# uWave.net
KiCad netlist of a schematic drawn in EAGLE
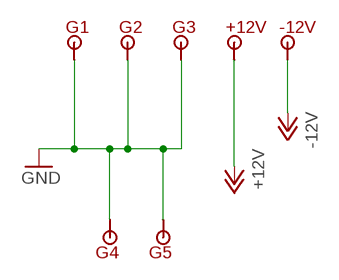
[diagram p0: schematic, sheet 1]
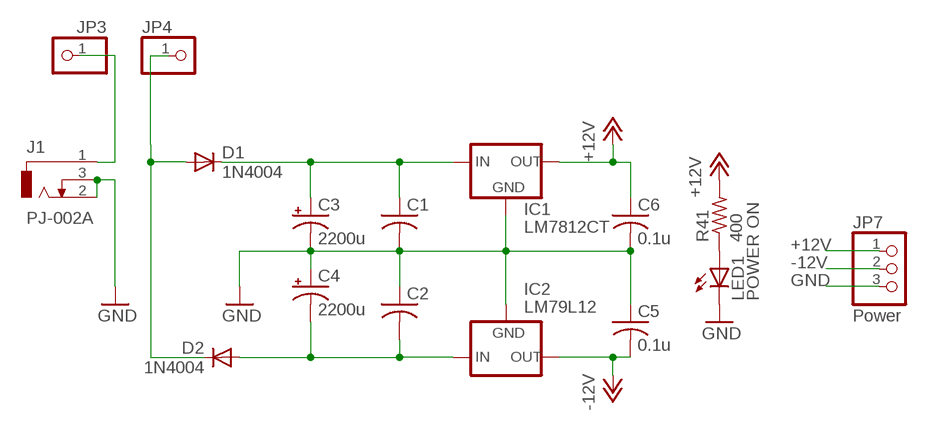
[diagram p1: schematic, sheet 2]
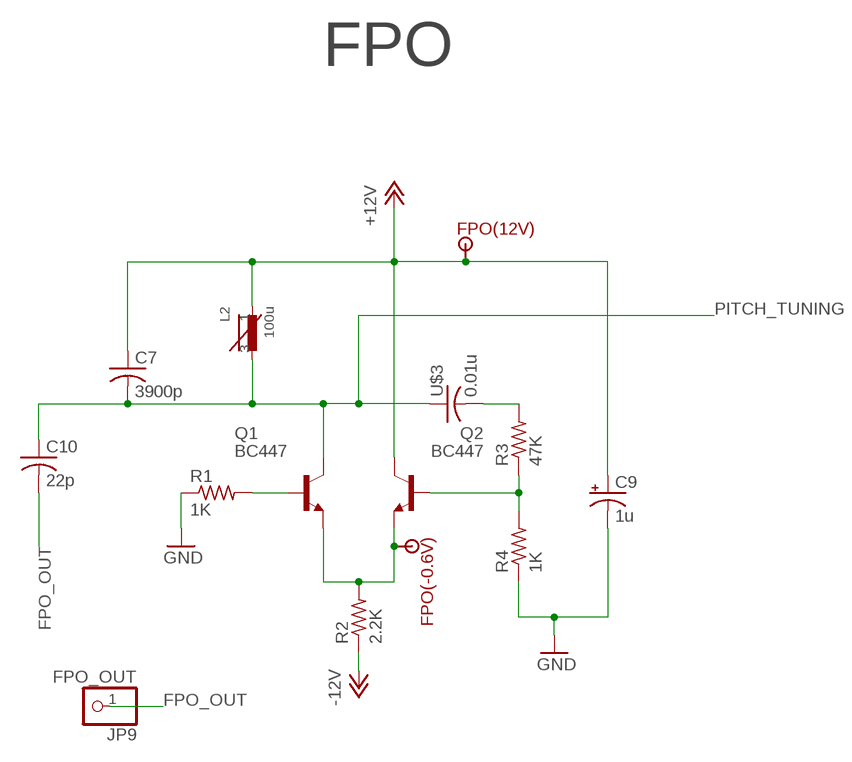
[diagram p2: schematic, sheet 3]
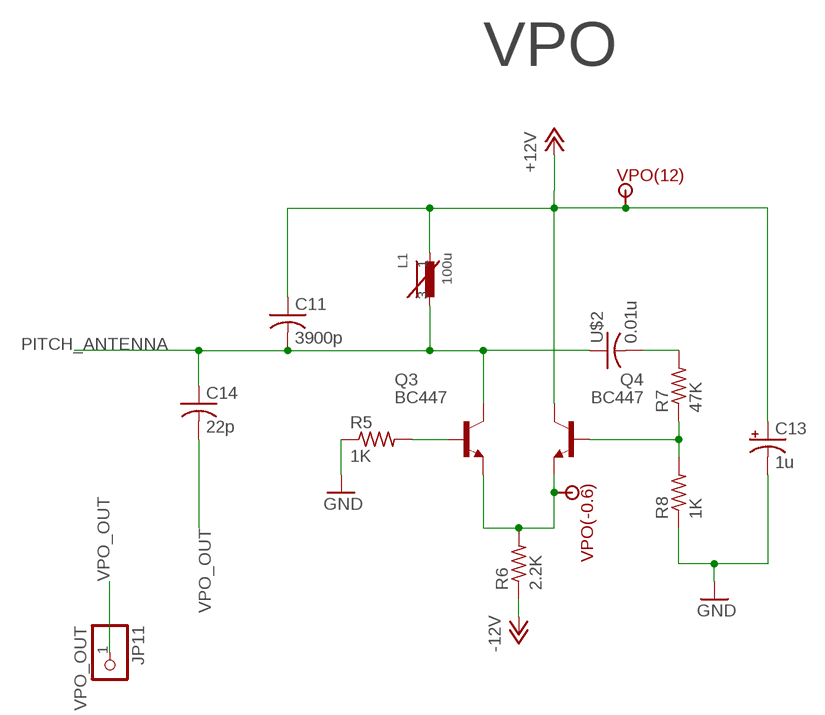
[diagram p3: schematic, sheet 4]
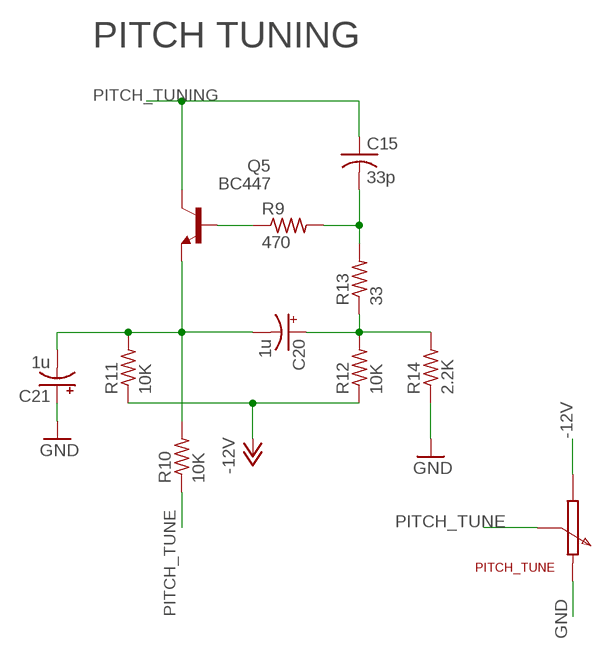
[diagram p4: schematic, sheet 5]
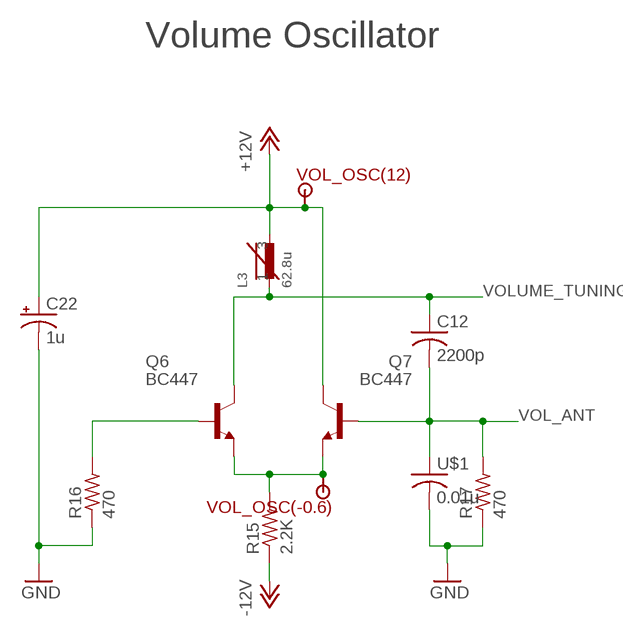
[diagram p5: schematic, sheet 6]
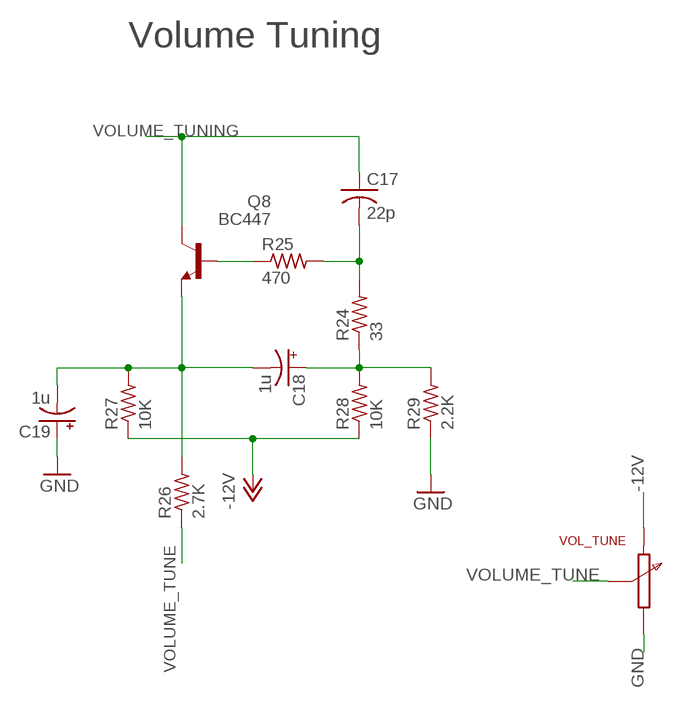
[diagram p6: schematic, sheet 7]
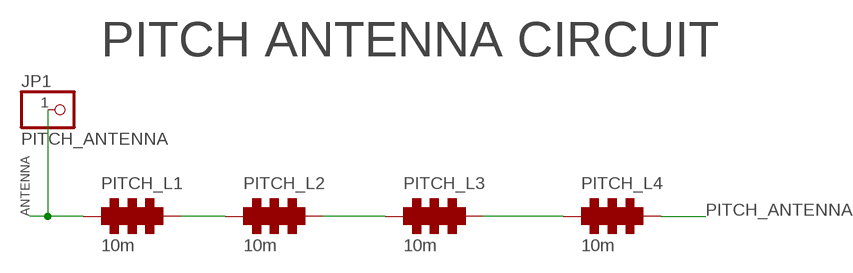
[diagram p7: schematic, sheet 8]
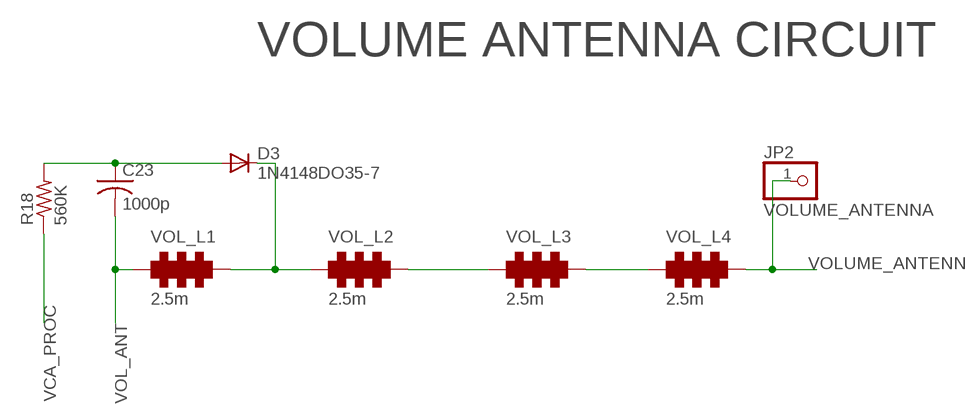
[diagram p8: schematic, sheet 9]
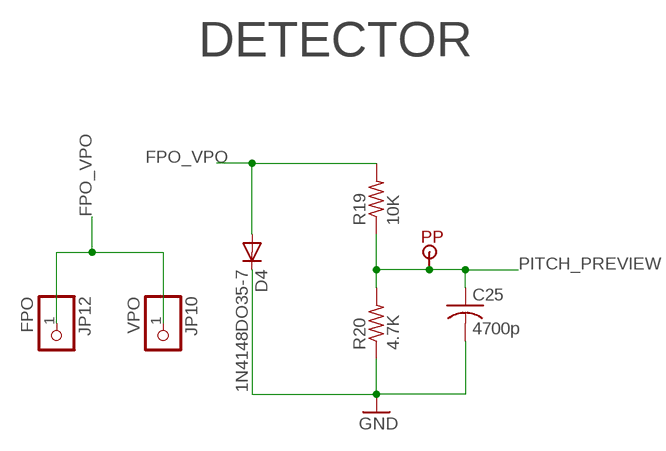
[diagram p9: schematic, sheet 10]
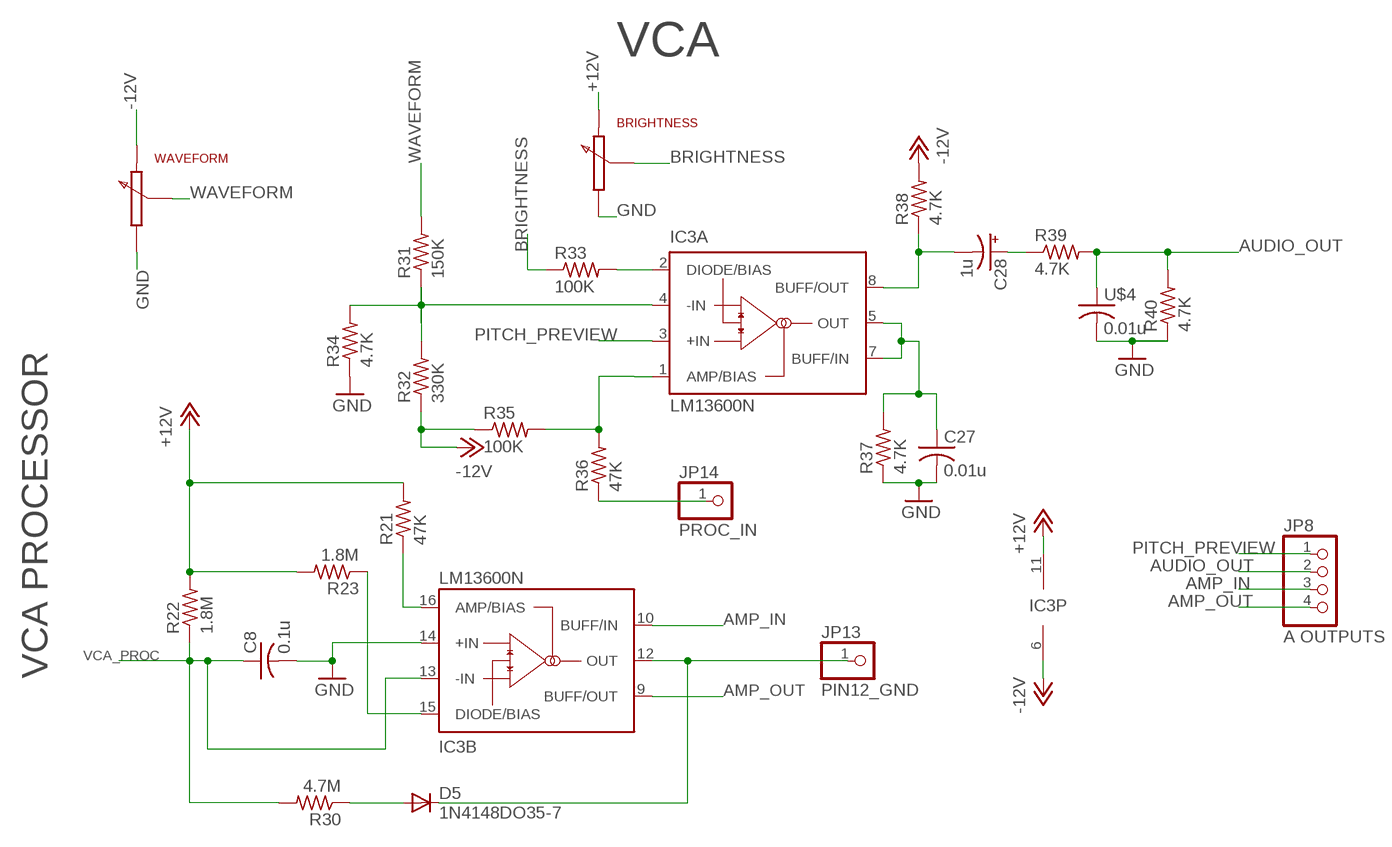
[diagram p10: schematic, sheet 11]

(export (version "E")
  (design (tool "Eeschema 10.0.6"))
  (components
    (comp (ref "JP1")
      (value "PITCH_ANTENNA")
      (footprint "eagle-import:1X01")
      (libsource (lib "eagle-import") (part "PINHD-1X1"))
    )
    (comp (ref "PITCH_L1")
      (value "10m")
      (footprint "eagle-import:INDUCTOR_CHOKE")
      (libsource (lib "eagle-import") (part "INDUCTOR_CHOKE"))
    )
    (comp (ref "PITCH_L2")
      (value "10m")
      (footprint "eagle-import:INDUCTOR_CHOKE")
      (libsource (lib "eagle-import") (part "INDUCTOR_CHOKE"))
    )
    (comp (ref "PITCH_L3")
      (value "10m")
      (footprint "eagle-import:INDUCTOR_CHOKE")
      (libsource (lib "eagle-import") (part "INDUCTOR_CHOKE"))
    )
    (comp (ref "PITCH_L4")
      (value "10m")
      (footprint "eagle-import:INDUCTOR_CHOKE")
      (libsource (lib "eagle-import") (part "INDUCTOR_CHOKE"))
    )
    (comp (ref "C7")
      (value "3900p")
      (footprint "eagle-import:C050-075X075")
      (libsource (lib "eagle-import") (part "C-US050-075X075"))
    )
    (comp (ref "C9")
      (value "1u")
      (footprint "eagle-import:E15-5")
      (libsource (lib "eagle-import") (part "CPOL-USE15-5AXIAL"))
    )
    (comp (ref "C10")
      (value "22p")
      (footprint "eagle-import:C050-025X075")
      (libsource (lib "eagle-import") (part "C-US050-025X075"))
    )
    (comp (ref "FPO(-0.6V)")
      (value "TEST1X1")
      (footprint "eagle-import:TP1X1")
      (libsource (lib "eagle-import") (part "TEST1X1"))
    )
    (comp (ref "FPO(12V)")
      (value "TEST1X1")
      (footprint "eagle-import:TP1X1")
      (libsource (lib "eagle-import") (part "TEST1X1"))
    )
    (comp (ref "JP9")
      (value "FPO_OUT")
      (footprint "eagle-import:1X01")
      (libsource (lib "eagle-import") (part "PINHD-1X1"))
    )
    (comp (ref "L2")
      (value "100u")
      (footprint "eagle-import:T1040Z")
      (libsource (lib "eagle-import") (part "TI040Z"))
    )
    (comp (ref "Q1")
      (value "BC447")
      (footprint "eagle-import:TO92-EBC")
      (libsource (lib "eagle-import") (part "BC447"))
    )
    (comp (ref "Q2")
      (value "BC447")
      (footprint "eagle-import:TO92-EBC")
      (libsource (lib "eagle-import") (part "BC447"))
    )
    (comp (ref "R1")
      (value "1K")
      (footprint "eagle-import:0207_10")
      (libsource (lib "eagle-import") (part "R-US_0207/10"))
    )
    (comp (ref "R2")
      (value "2.2K")
      (footprint "eagle-import:0207_10")
      (libsource (lib "eagle-import") (part "R-US_0207/10"))
    )
    (comp (ref "R3")
      (value "47K")
      (footprint "eagle-import:0207_10")
      (libsource (lib "eagle-import") (part "R-US_0207/10"))
    )
    (comp (ref "R4")
      (value "1K")
      (footprint "eagle-import:0207_10")
      (libsource (lib "eagle-import") (part "R-US_0207/10"))
    )
    (comp (ref "U$3")
      (value "0.01u")
      (footprint "eagle-import:QXY")
      (libsource (lib "eagle-import") (part "QXY103"))
    )
    (comp (ref "C17")
      (value "22p")
      (footprint "eagle-import:C025-040X050")
      (libsource (lib "eagle-import") (part "C-US025-040X050"))
    )
    (comp (ref "C18")
      (value "1u")
      (footprint "eagle-import:E15-5")
      (libsource (lib "eagle-import") (part "CPOL-USE15-5AXIAL"))
    )
    (comp (ref "C19")
      (value "1u")
      (footprint "eagle-import:E15-5")
      (libsource (lib "eagle-import") (part "CPOL-USE15-5AXIAL"))
    )
    (comp (ref "Q8")
      (value "BC447")
      (footprint "eagle-import:TO92-EBC")
      (libsource (lib "eagle-import") (part "BC447"))
    )
    (comp (ref "R24")
      (value "33")
      (footprint "eagle-import:0207_10")
      (libsource (lib "eagle-import") (part "R-US_0207/10"))
    )
    (comp (ref "R25")
      (value "470")
      (footprint "eagle-import:0207_10")
      (libsource (lib "eagle-import") (part "R-US_0207/10"))
    )
    (comp (ref "R26")
      (value "2.7K")
      (footprint "eagle-import:0207_10")
      (libsource (lib "eagle-import") (part "R-US_0207/10"))
    )
    (comp (ref "R27")
      (value "10K")
      (footprint "eagle-import:0207_10")
      (libsource (lib "eagle-import") (part "R-US_0207/10"))
    )
    (comp (ref "R28")
      (value "10K")
      (footprint "eagle-import:0207_10")
      (libsource (lib "eagle-import") (part "R-US_0207/10"))
    )
    (comp (ref "R29")
      (value "2.2K")
      (footprint "eagle-import:0207_10")
      (libsource (lib "eagle-import") (part "R-US_0207/10"))
    )
    (comp (ref "VOL_TUNE")
      (value "POT")
      (footprint "eagle-import:EVUE")
      (libsource (lib "eagle-import") (part "POT"))
    )
    (comp (ref "C25")
      (value "4700p")
      (footprint "eagle-import:C025-025X050")
      (libsource (lib "eagle-import") (part "C-US025-025X050"))
    )
    (comp (ref "D4")
      (value "1N4148DO35-7")
      (footprint "eagle-import:DO35-7")
      (libsource (lib "eagle-import") (part "1N4148DO35-7"))
    )
    (comp (ref "JP10")
      (value "VPO")
      (footprint "eagle-import:1X01")
      (libsource (lib "eagle-import") (part "PINHD-1X1"))
    )
    (comp (ref "JP12")
      (value "FPO")
      (footprint "eagle-import:1X01")
      (libsource (lib "eagle-import") (part "PINHD-1X1"))
    )
    (comp (ref "PP")
      (value "TEST1X1")
      (footprint "eagle-import:TP1X1")
      (libsource (lib "eagle-import") (part "TEST1X1"))
    )
    (comp (ref "R19")
      (value "10K")
      (footprint "eagle-import:0207_10")
      (libsource (lib "eagle-import") (part "R-US_0207/10"))
    )
    (comp (ref "R20")
      (value "4.7K")
      (footprint "eagle-import:0207_10")
      (libsource (lib "eagle-import") (part "R-US_0207/10"))
    )
    (comp (ref "C15")
      (value "33p")
      (footprint "eagle-import:C025-040X050")
      (libsource (lib "eagle-import") (part "C-US025-040X050"))
    )
    (comp (ref "C20")
      (value "1u")
      (footprint "eagle-import:E15-5")
      (libsource (lib "eagle-import") (part "CPOL-USE15-5AXIAL"))
    )
    (comp (ref "C21")
      (value "1u")
      (footprint "eagle-import:E15-5")
      (libsource (lib "eagle-import") (part "CPOL-USE15-5AXIAL"))
    )
    (comp (ref "PITCH_TUNE")
      (value "POT")
      (footprint "eagle-import:EVUE")
      (libsource (lib "eagle-import") (part "POT"))
    )
    (comp (ref "Q5")
      (value "BC447")
      (footprint "eagle-import:TO92-EBC")
      (libsource (lib "eagle-import") (part "BC447"))
    )
    (comp (ref "R9")
      (value "470")
      (footprint "eagle-import:0207_10")
      (libsource (lib "eagle-import") (part "R-US_0207/10"))
    )
    (comp (ref "R10")
      (value "10K")
      (footprint "eagle-import:0207_10")
      (libsource (lib "eagle-import") (part "R-US_0207/10"))
    )
    (comp (ref "R11")
      (value "10K")
      (footprint "eagle-import:0207_10")
      (libsource (lib "eagle-import") (part "R-US_0207/10"))
    )
    (comp (ref "R12")
      (value "10K")
      (footprint "eagle-import:0207_10")
      (libsource (lib "eagle-import") (part "R-US_0207/10"))
    )
    (comp (ref "R13")
      (value "33")
      (footprint "eagle-import:0207_10")
      (libsource (lib "eagle-import") (part "R-US_0207/10"))
    )
    (comp (ref "R14")
      (value "2.2K")
      (footprint "eagle-import:0207_10")
      (libsource (lib "eagle-import") (part "R-US_0207/10"))
    )
    (comp (ref "C11")
      (value "3900p")
      (footprint "eagle-import:C050-075X075")
      (libsource (lib "eagle-import") (part "C-US050-075X075"))
    )
    (comp (ref "C13")
      (value "1u")
      (footprint "eagle-import:E15-5")
      (libsource (lib "eagle-import") (part "CPOL-USE15-5AXIAL"))
    )
    (comp (ref "C14")
      (value "22p")
      (footprint "eagle-import:C050-025X075")
      (libsource (lib "eagle-import") (part "C-US050-025X075"))
    )
    (comp (ref "JP11")
      (value "VPO_OUT")
      (footprint "eagle-import:1X01")
      (libsource (lib "eagle-import") (part "PINHD-1X1"))
    )
    (comp (ref "L1")
      (value "100u")
      (footprint "eagle-import:T1040Z")
      (libsource (lib "eagle-import") (part "TI040Z"))
    )
    (comp (ref "Q3")
      (value "BC447")
      (footprint "eagle-import:TO92-EBC")
      (libsource (lib "eagle-import") (part "BC447"))
    )
    (comp (ref "Q4")
      (value "BC447")
      (footprint "eagle-import:TO92-EBC")
      (libsource (lib "eagle-import") (part "BC447"))
    )
    (comp (ref "R5")
      (value "1K")
      (footprint "eagle-import:0207_10")
      (libsource (lib "eagle-import") (part "R-US_0207/10"))
    )
    (comp (ref "R6")
      (value "2.2K")
      (footprint "eagle-import:0207_10")
      (libsource (lib "eagle-import") (part "R-US_0207/10"))
    )
    (comp (ref "R7")
      (value "47K")
      (footprint "eagle-import:0207_10")
      (libsource (lib "eagle-import") (part "R-US_0207/10"))
    )
    (comp (ref "R8")
      (value "1K")
      (footprint "eagle-import:0207_10")
      (libsource (lib "eagle-import") (part "R-US_0207/10"))
    )
    (comp (ref "U$2")
      (value "0.01u")
      (footprint "eagle-import:QXY")
      (libsource (lib "eagle-import") (part "QXY103"))
    )
    (comp (ref "VPO(-0.6)")
      (value "TEST1X1")
      (footprint "eagle-import:TP1X1")
      (libsource (lib "eagle-import") (part "TEST1X1"))
    )
    (comp (ref "VPO(12)")
      (value "TEST1X1")
      (footprint "eagle-import:TP1X1")
      (libsource (lib "eagle-import") (part "TEST1X1"))
    )
    (comp (ref "BRIGHTNESS")
      (value "POT")
      (footprint "eagle-import:EVUE")
      (libsource (lib "eagle-import") (part "POT"))
    )
    (comp (ref "C8")
      (value "0.1u")
      (footprint "eagle-import:C025-024X044")
      (libsource (lib "eagle-import") (part "C-US025-024X044"))
    )
    (comp (ref "C27")
      (value "0.01u")
      (footprint "eagle-import:C050-024X044")
      (libsource (lib "eagle-import") (part "C-US050-024X044"))
    )
    (comp (ref "C28")
      (value "1u")
      (footprint "eagle-import:E15-5")
      (libsource (lib "eagle-import") (part "resistor_CPOL-USE15-5AXIAL"))
    )
    (comp (ref "D5")
      (value "1N4148DO35-7")
      (footprint "eagle-import:DO35-7")
      (libsource (lib "eagle-import") (part "1N4148DO35-7"))
    )
    (comp (ref "IC3")
      (value "LM13600N")
      (footprint "eagle-import:DIL16")
      (libsource (lib "eagle-import") (part "LM13600N"))
    )
    (comp (ref "JP8")
      (value "A OUTPUTS")
      (footprint "eagle-import:1X04")
      (libsource (lib "eagle-import") (part "PINHD-1X4"))
    )
    (comp (ref "JP13")
      (value "PIN12_GND")
      (footprint "eagle-import:1X01")
      (libsource (lib "eagle-import") (part "PINHD-1X1"))
    )
    (comp (ref "JP14")
      (value "PROC_IN")
      (footprint "eagle-import:1X01")
      (libsource (lib "eagle-import") (part "PINHD-1X1"))
    )
    (comp (ref "R21")
      (value "47K")
      (footprint "eagle-import:0207_10")
      (libsource (lib "eagle-import") (part "R-US_0207/10"))
    )
    (comp (ref "R22")
      (value "1.8M")
      (footprint "eagle-import:0207_10")
      (libsource (lib "eagle-import") (part "R-US_0207/10"))
    )
    (comp (ref "R23")
      (value "1.8M")
      (footprint "eagle-import:0207_10")
      (libsource (lib "eagle-import") (part "R-US_0207/10"))
    )
    (comp (ref "R30")
      (value "4.7M")
      (footprint "eagle-import:0207_10")
      (libsource (lib "eagle-import") (part "R-US_0207/10"))
    )
    (comp (ref "R31")
      (value "150K")
      (footprint "eagle-import:0207_10")
      (libsource (lib "eagle-import") (part "R-US_0207/10"))
    )
    (comp (ref "R32")
      (value "330K")
      (footprint "eagle-import:0207_10")
      (libsource (lib "eagle-import") (part "R-US_0207/10"))
    )
    (comp (ref "R33")
      (value "100K")
      (footprint "eagle-import:0207_10")
      (libsource (lib "eagle-import") (part "R-US_0207/10"))
    )
    (comp (ref "R34")
      (value "4.7K")
      (footprint "eagle-import:0207_10")
      (libsource (lib "eagle-import") (part "R-US_0207/10"))
    )
    (comp (ref "R35")
      (value "100K")
      (footprint "eagle-import:0207_10")
      (libsource (lib "eagle-import") (part "R-US_0207/10"))
    )
    (comp (ref "R36")
      (value "47K")
      (footprint "eagle-import:0207_10")
      (libsource (lib "eagle-import") (part "R-US_0207/10"))
    )
    (comp (ref "R37")
      (value "4.7K")
      (footprint "eagle-import:0207_10")
      (libsource (lib "eagle-import") (part "R-US_0207/10"))
    )
    (comp (ref "R38")
      (value "4.7K")
      (footprint "eagle-import:0207_10")
      (libsource (lib "eagle-import") (part "R-US_0207/10"))
    )
    (comp (ref "R39")
      (value "4.7K")
      (footprint "eagle-import:0207_10")
      (libsource (lib "eagle-import") (part "R-US_0207/10"))
    )
    (comp (ref "R40")
      (value "4.7K")
      (footprint "eagle-import:0207_10")
      (libsource (lib "eagle-import") (part "R-US_0207/10"))
    )
    (comp (ref "U$4")
      (value "0.01u")
      (footprint "eagle-import:QXY")
      (libsource (lib "eagle-import") (part "QXY103"))
    )
    (comp (ref "WAVEFORM")
      (value "POT")
      (footprint "eagle-import:EVUE")
      (libsource (lib "eagle-import") (part "POT"))
    )
    (comp (ref "C1")
      (value "C-US050-024X044")
      (footprint "eagle-import:C050-024X044")
      (libsource (lib "eagle-import") (part "C-US050-024X044"))
    )
    (comp (ref "C2")
      (value "C-US050-024X044")
      (footprint "eagle-import:C050-024X044")
      (libsource (lib "eagle-import") (part "C-US050-024X044"))
    )
    (comp (ref "C3")
      (value "2200u")
      (footprint "eagle-import:E7,5-16")
      (libsource (lib "eagle-import") (part "CPOL-USE7.5-16"))
    )
    (comp (ref "C4")
      (value "2200u")
      (footprint "eagle-import:E7,5-16")
      (libsource (lib "eagle-import") (part "CPOL-USE7.5-16"))
    )
    (comp (ref "C5")
      (value "0.1u")
      (footprint "eagle-import:C025-024X044")
      (libsource (lib "eagle-import") (part "C-US025-024X044"))
    )
    (comp (ref "C6")
      (value "0.1u")
      (footprint "eagle-import:C025-024X044")
      (libsource (lib "eagle-import") (part "C-US025-024X044"))
    )
    (comp (ref "D1")
      (value "1N4004")
      (footprint "eagle-import:DO41-10")
      (libsource (lib "eagle-import") (part "1N4004"))
    )
    (comp (ref "D2")
      (value "1N4004")
      (footprint "eagle-import:DO41-10")
      (libsource (lib "eagle-import") (part "1N4004"))
    )
    (comp (ref "IC1")
      (value "LM7812CT")
      (footprint "eagle-import:78XXS")
      (libsource (lib "eagle-import") (part "78XXS"))
    )
    (comp (ref "IC2")
      (value "LM79L12")
      (footprint "eagle-import:79XXS")
      (libsource (lib "eagle-import") (part "79XXS"))
    )
    (comp (ref "J1")
      (value "PJ-002A")
      (footprint "eagle-import:PJ-002A")
      (libsource (lib "eagle-import") (part "PJ-002A"))
    )
    (comp (ref "JP3")
      (value "PINHD-1X1")
      (footprint "eagle-import:1X01")
      (libsource (lib "eagle-import") (part "PINHD-1X1"))
    )
    (comp (ref "JP4")
      (value "PINHD-1X1")
      (footprint "eagle-import:1X01")
      (libsource (lib "eagle-import") (part "PINHD-1X1"))
    )
    (comp (ref "JP7")
      (value "Power")
      (footprint "eagle-import:1X03")
      (libsource (lib "eagle-import") (part "PINHD-1X3"))
    )
    (comp (ref "LED1")
      (value "POWER ON")
      (footprint "eagle-import:LED3MM")
      (libsource (lib "eagle-import") (part "LED3MM"))
    )
    (comp (ref "R41")
      (value "400")
      (footprint "eagle-import:0207_10")
      (libsource (lib "eagle-import") (part "R-US_0207/10"))
    )
    (comp (ref "C12")
      (value "2200p")
      (footprint "eagle-import:C075-032X103")
      (libsource (lib "eagle-import") (part "C-US075-032X103"))
    )
    (comp (ref "C22")
      (value "1u")
      (footprint "eagle-import:E15-5")
      (libsource (lib "eagle-import") (part "CPOL-USE15-5AXIAL"))
    )
    (comp (ref "L3")
      (value "62.8u")
      (footprint "eagle-import:SLOT-TEN-5-10")
      (libsource (lib "eagle-import") (part "SLOT-TEN"))
    )
    (comp (ref "Q6")
      (value "BC447")
      (footprint "eagle-import:TO92-EBC")
      (libsource (lib "eagle-import") (part "BC447"))
    )
    (comp (ref "Q7")
      (value "BC447")
      (footprint "eagle-import:TO92-EBC")
      (libsource (lib "eagle-import") (part "BC447"))
    )
    (comp (ref "R15")
      (value "2.2K")
      (footprint "eagle-import:0207_10")
      (libsource (lib "eagle-import") (part "R-US_0207/10"))
    )
    (comp (ref "R16")
      (value "470")
      (footprint "eagle-import:0207_10")
      (libsource (lib "eagle-import") (part "R-US_0207/10"))
    )
    (comp (ref "R17")
      (value "470")
      (footprint "eagle-import:0207_10")
      (libsource (lib "eagle-import") (part "R-US_0207/10"))
    )
    (comp (ref "U$1")
      (value "0.01u")
      (footprint "eagle-import:QXY")
      (libsource (lib "eagle-import") (part "QXY103"))
    )
    (comp (ref "VOL_OSC(-0.6)")
      (value "TEST1X1")
      (footprint "eagle-import:TP1X1")
      (libsource (lib "eagle-import") (part "TEST1X1"))
    )
    (comp (ref "VOL_OSC(12)")
      (value "TEST1X1")
      (footprint "eagle-import:TP1X1")
      (libsource (lib "eagle-import") (part "TEST1X1"))
    )
    (comp (ref "+12V")
      (value "TEST1X1")
      (footprint "eagle-import:TP1X1")
      (libsource (lib "eagle-import") (part "TEST1X1"))
    )
    (comp (ref "-12V")
      (value "TEST1X1")
      (footprint "eagle-import:TP1X1")
      (libsource (lib "eagle-import") (part "TEST1X1"))
    )
    (comp (ref "G1")
      (value "TEST1X1")
      (footprint "eagle-import:TP1X1")
      (libsource (lib "eagle-import") (part "TEST1X1"))
    )
    (comp (ref "G2")
      (value "TEST1X1")
      (footprint "eagle-import:TP1X1")
      (libsource (lib "eagle-import") (part "TEST1X1"))
    )
    (comp (ref "G3")
      (value "TEST1X1")
      (footprint "eagle-import:TP1X1")
      (libsource (lib "eagle-import") (part "TEST1X1"))
    )
    (comp (ref "G4")
      (value "TEST1X1")
      (footprint "eagle-import:TP1X1")
      (libsource (lib "eagle-import") (part "TEST1X1"))
    )
    (comp (ref "G5")
      (value "TEST1X1")
      (footprint "eagle-import:TP1X1")
      (libsource (lib "eagle-import") (part "TEST1X1"))
    )
    (comp (ref "C23")
      (value "1000p")
      (footprint "eagle-import:C025-024X044")
      (libsource (lib "eagle-import") (part "C-US025-024X044"))
    )
    (comp (ref "D3")
      (value "1N4148DO35-7")
      (footprint "eagle-import:DO35-7")
      (libsource (lib "eagle-import") (part "1N4148DO35-7"))
    )
    (comp (ref "JP2")
      (value "VOLUME_ANTENNA")
      (footprint "eagle-import:1X01")
      (libsource (lib "eagle-import") (part "PINHD-1X1"))
    )
    (comp (ref "R18")
      (value "560K")
      (footprint "eagle-import:0207_10")
      (libsource (lib "eagle-import") (part "R-US_0207/10"))
    )
    (comp (ref "VOL_L1")
      (value "2.5m")
      (footprint "eagle-import:INDUCTOR_CHOKE")
      (libsource (lib "eagle-import") (part "INDUCTOR_CHOKE"))
    )
    (comp (ref "VOL_L2")
      (value "2.5m")
      (footprint "eagle-import:INDUCTOR_CHOKE")
      (libsource (lib "eagle-import") (part "INDUCTOR_CHOKE"))
    )
    (comp (ref "VOL_L3")
      (value "2.5m")
      (footprint "eagle-import:INDUCTOR_CHOKE")
      (libsource (lib "eagle-import") (part "INDUCTOR_CHOKE"))
    )
    (comp (ref "VOL_L4")
      (value "2.5m")
      (footprint "eagle-import:INDUCTOR_CHOKE")
      (libsource (lib "eagle-import") (part "INDUCTOR_CHOKE"))
    )
  )
  (nets
    (net (code "1") (name "+12V") (class "Default")
      (node (ref "+12V") (pin "P$1") (pinfunction "P$1_P$1") (pintype "bidirectional"))
      (node (ref "BRIGHTNESS") (pin "1") (pinfunction "P$1_1") (pintype "bidirectional"))
      (node (ref "C11") (pin "1") (pinfunction "1_1") (pintype "passive"))
      (node (ref "C13") (pin "+") (pinfunction "+_+") (pintype "passive"))
      (node (ref "C22") (pin "+") (pinfunction "+_+") (pintype "passive"))
      (node (ref "C6") (pin "1") (pinfunction "1_1") (pintype "passive"))
      (node (ref "C7") (pin "1") (pinfunction "1_1") (pintype "passive"))
      (node (ref "C9") (pin "+") (pinfunction "+_+") (pintype "passive"))
      (node (ref "FPO(12V)") (pin "P$1") (pinfunction "P$1_P$1") (pintype "bidirectional"))
      (node (ref "IC1") (pin "OUT") (pinfunction "OUT_OUT") (pintype "passive"))
      (node (ref "IC3") (pin "11") (pinfunction "V+_11") (pintype "power_in"))
      (node (ref "JP7") (pin "1") (pinfunction "1_1") (pintype "passive"))
      (node (ref "L1") (pin "1") (pinfunction "1_1") (pintype "bidirectional"))
      (node (ref "L2") (pin "1") (pinfunction "1_1") (pintype "bidirectional"))
      (node (ref "L3") (pin "3") (pinfunction "3_3") (pintype "bidirectional"))
      (node (ref "Q2") (pin "C") (pinfunction "C_C") (pintype "passive"))
      (node (ref "Q4") (pin "C") (pinfunction "C_C") (pintype "passive"))
      (node (ref "Q7") (pin "C") (pinfunction "C_C") (pintype "passive"))
      (node (ref "R21") (pin "2") (pinfunction "2_2") (pintype "passive"))
      (node (ref "R22") (pin "2") (pinfunction "2_2") (pintype "passive"))
      (node (ref "R23") (pin "2") (pinfunction "2_2") (pintype "passive"))
      (node (ref "R41") (pin "2") (pinfunction "2_2") (pintype "passive"))
      (node (ref "VOL_OSC(12)") (pin "P$1") (pinfunction "P$1_P$1") (pintype "bidirectional"))
      (node (ref "VPO(12)") (pin "P$1") (pinfunction "P$1_P$1") (pintype "bidirectional"))
    )
    (net (code "2") (name "-12V") (class "Default")
      (node (ref "-12V") (pin "P$1") (pinfunction "P$1_P$1") (pintype "bidirectional"))
      (node (ref "C5") (pin "2") (pinfunction "2_2") (pintype "passive"))
      (node (ref "IC2") (pin "OUT") (pinfunction "OUT_OUT") (pintype "passive"))
      (node (ref "IC3") (pin "6") (pinfunction "V-_6") (pintype "power_in"))
      (node (ref "JP7") (pin "2") (pinfunction "2_2") (pintype "passive"))
      (node (ref "PITCH_TUNE") (pin "3") (pinfunction "P$3_3") (pintype "bidirectional"))
      (node (ref "R11") (pin "1") (pinfunction "1_1") (pintype "passive"))
      (node (ref "R12") (pin "1") (pinfunction "1_1") (pintype "passive"))
      (node (ref "R15") (pin "1") (pinfunction "1_1") (pintype "passive"))
      (node (ref "R2") (pin "1") (pinfunction "1_1") (pintype "passive"))
      (node (ref "R27") (pin "1") (pinfunction "1_1") (pintype "passive"))
      (node (ref "R28") (pin "1") (pinfunction "1_1") (pintype "passive"))
      (node (ref "R32") (pin "1") (pinfunction "1_1") (pintype "passive"))
      (node (ref "R35") (pin "1") (pinfunction "1_1") (pintype "passive"))
      (node (ref "R38") (pin "2") (pinfunction "2_2") (pintype "passive"))
      (node (ref "R6") (pin "1") (pinfunction "1_1") (pintype "passive"))
      (node (ref "VOL_TUNE") (pin "1") (pinfunction "P$1_1") (pintype "bidirectional"))
      (node (ref "WAVEFORM") (pin "1") (pinfunction "P$1_1") (pintype "bidirectional"))
    )
    (net (code "3") (name "AMP_IN") (class "Default")
      (node (ref "IC3") (pin "10") (pinfunction "BUFF/IN_10") (pintype "input"))
      (node (ref "JP8") (pin "3") (pinfunction "3_3") (pintype "passive"))
    )
    (net (code "4") (name "AMP_OUT") (class "Default")
      (node (ref "IC3") (pin "9") (pinfunction "BUFF/OUT_9") (pintype "output"))
      (node (ref "JP8") (pin "4") (pinfunction "4_4") (pintype "passive"))
    )
    (net (code "5") (name "ANTENNA") (class "Default")
      (node (ref "JP1") (pin "1") (pinfunction "1_1") (pintype "passive"))
      (node (ref "PITCH_L1") (pin "P$1") (pinfunction "P$1_P$1") (pintype "bidirectional"))
    )
    (net (code "6") (name "AUDIO_OUT") (class "Default")
      (node (ref "JP8") (pin "2") (pinfunction "2_2") (pintype "passive"))
      (node (ref "R39") (pin "2") (pinfunction "2_2") (pintype "passive"))
      (node (ref "R40") (pin "2") (pinfunction "2_2") (pintype "passive"))
      (node (ref "U$4") (pin "P$1") (pinfunction "1_P$1") (pintype "passive"))
    )
    (net (code "7") (name "BRIGHTNESS") (class "Default")
      (node (ref "BRIGHTNESS") (pin "2") (pinfunction "P$2_2") (pintype "bidirectional"))
      (node (ref "R33") (pin "1") (pinfunction "1_1") (pintype "passive"))
    )
    (net (code "8") (name "FPO_OUT") (class "Default")
      (node (ref "C10") (pin "2") (pinfunction "2_2") (pintype "passive"))
      (node (ref "JP9") (pin "1") (pinfunction "1_1") (pintype "passive"))
    )
    (net (code "9") (name "FPO_VPO") (class "Default")
      (node (ref "D4") (pin "A") (pinfunction "A_A") (pintype "passive"))
      (node (ref "JP10") (pin "1") (pinfunction "1_1") (pintype "passive"))
      (node (ref "JP12") (pin "1") (pinfunction "1_1") (pintype "passive"))
      (node (ref "R19") (pin "2") (pinfunction "2_2") (pintype "passive"))
    )
    (net (code "10") (name "GND") (class "Default")
      (node (ref "BRIGHTNESS") (pin "3") (pinfunction "P$3_3") (pintype "bidirectional"))
      (node (ref "C1") (pin "2") (pinfunction "2_2") (pintype "passive"))
      (node (ref "C13") (pin "-") (pinfunction "-_-") (pintype "passive"))
      (node (ref "C19") (pin "+") (pinfunction "+_+") (pintype "passive"))
      (node (ref "C2") (pin "1") (pinfunction "1_1") (pintype "passive"))
      (node (ref "C21") (pin "+") (pinfunction "+_+") (pintype "passive"))
      (node (ref "C22") (pin "-") (pinfunction "-_-") (pintype "passive"))
      (node (ref "C25") (pin "2") (pinfunction "2_2") (pintype "passive"))
      (node (ref "C27") (pin "2") (pinfunction "2_2") (pintype "passive"))
      (node (ref "C3") (pin "-") (pinfunction "-_-") (pintype "passive"))
      (node (ref "C4") (pin "+") (pinfunction "+_+") (pintype "passive"))
      (node (ref "C5") (pin "1") (pinfunction "1_1") (pintype "passive"))
      (node (ref "C6") (pin "2") (pinfunction "2_2") (pintype "passive"))
      (node (ref "C8") (pin "2") (pinfunction "2_2") (pintype "passive"))
      (node (ref "C9") (pin "-") (pinfunction "-_-") (pintype "passive"))
      (node (ref "D4") (pin "C") (pinfunction "C_C") (pintype "passive"))
      (node (ref "G1") (pin "P$1") (pinfunction "P$1_P$1") (pintype "bidirectional"))
      (node (ref "G2") (pin "P$1") (pinfunction "P$1_P$1") (pintype "bidirectional"))
      (node (ref "G3") (pin "P$1") (pinfunction "P$1_P$1") (pintype "bidirectional"))
      (node (ref "G4") (pin "P$1") (pinfunction "P$1_P$1") (pintype "bidirectional"))
      (node (ref "G5") (pin "P$1") (pinfunction "P$1_P$1") (pintype "bidirectional"))
      (node (ref "IC1") (pin "GND") (pinfunction "GND_GND") (pintype "input"))
      (node (ref "IC2") (pin "GND") (pinfunction "GND_GND") (pintype "input"))
      (node (ref "IC3") (pin "14") (pinfunction "+IN_14") (pintype "input"))
      (node (ref "J1") (pin "2") (pinfunction "2_2") (pintype "bidirectional"))
      (node (ref "J1") (pin "3") (pinfunction "3_3") (pintype "bidirectional"))
      (node (ref "JP7") (pin "3") (pinfunction "3_3") (pintype "passive"))
      (node (ref "LED1") (pin "K") (pinfunction "C_K") (pintype "passive"))
      (node (ref "PITCH_TUNE") (pin "1") (pinfunction "P$1_1") (pintype "bidirectional"))
      (node (ref "R1") (pin "1") (pinfunction "1_1") (pintype "passive"))
      (node (ref "R14") (pin "1") (pinfunction "1_1") (pintype "passive"))
      (node (ref "R16") (pin "1") (pinfunction "1_1") (pintype "passive"))
      (node (ref "R17") (pin "1") (pinfunction "1_1") (pintype "passive"))
      (node (ref "R20") (pin "1") (pinfunction "1_1") (pintype "passive"))
      (node (ref "R29") (pin "1") (pinfunction "1_1") (pintype "passive"))
      (node (ref "R34") (pin "1") (pinfunction "1_1") (pintype "passive"))
      (node (ref "R37") (pin "1") (pinfunction "1_1") (pintype "passive"))
      (node (ref "R4") (pin "1") (pinfunction "1_1") (pintype "passive"))
      (node (ref "R40") (pin "1") (pinfunction "1_1") (pintype "passive"))
      (node (ref "R5") (pin "1") (pinfunction "1_1") (pintype "passive"))
      (node (ref "R8") (pin "1") (pinfunction "1_1") (pintype "passive"))
      (node (ref "U$1") (pin "P$2") (pinfunction "2_P$2") (pintype "passive"))
      (node (ref "U$4") (pin "P$2") (pinfunction "2_P$2") (pintype "passive"))
      (node (ref "VOL_TUNE") (pin "3") (pinfunction "P$3_3") (pintype "bidirectional"))
      (node (ref "WAVEFORM") (pin "3") (pinfunction "P$3_3") (pintype "bidirectional"))
    )
    (net (code "11") (name "Net-(C1-Pad1)") (class "Default")
      (node (ref "C1") (pin "1") (pinfunction "1_1") (pintype "passive"))
      (node (ref "C3") (pin "+") (pinfunction "+_+") (pintype "passive"))
      (node (ref "D1") (pin "C") (pinfunction "C_C") (pintype "passive"))
      (node (ref "IC1") (pin "IN") (pinfunction "IN_IN") (pintype "input"))
    )
    (net (code "12") (name "Net-(C2-Pad2)") (class "Default")
      (node (ref "C2") (pin "2") (pinfunction "2_2") (pintype "passive"))
      (node (ref "C4") (pin "-") (pinfunction "-_-") (pintype "passive"))
      (node (ref "D2") (pin "A") (pinfunction "A_A") (pintype "passive"))
      (node (ref "IC2") (pin "IN") (pinfunction "IN_IN") (pintype "input"))
    )
    (net (code "13") (name "Net-(C15-Pad2)") (class "Default")
      (node (ref "C15") (pin "2") (pinfunction "2_2") (pintype "passive"))
      (node (ref "R13") (pin "2") (pinfunction "2_2") (pintype "passive"))
      (node (ref "R9") (pin "2") (pinfunction "2_2") (pintype "passive"))
    )
    (net (code "14") (name "Net-(C17-Pad2)") (class "Default")
      (node (ref "C17") (pin "2") (pinfunction "2_2") (pintype "passive"))
      (node (ref "R24") (pin "2") (pinfunction "2_2") (pintype "passive"))
      (node (ref "R25") (pin "2") (pinfunction "2_2") (pintype "passive"))
    )
    (net (code "15") (name "Net-(C18-Pad+)") (class "Default")
      (node (ref "C18") (pin "+") (pinfunction "+_+") (pintype "passive"))
      (node (ref "R24") (pin "1") (pinfunction "1_1") (pintype "passive"))
      (node (ref "R28") (pin "2") (pinfunction "2_2") (pintype "passive"))
      (node (ref "R29") (pin "2") (pinfunction "2_2") (pintype "passive"))
    )
    (net (code "16") (name "Net-(C18-Pad-)") (class "Default")
      (node (ref "C18") (pin "-") (pinfunction "-_-") (pintype "passive"))
      (node (ref "C19") (pin "-") (pinfunction "-_-") (pintype "passive"))
      (node (ref "Q8") (pin "E") (pinfunction "E_E") (pintype "passive"))
      (node (ref "R26") (pin "2") (pinfunction "2_2") (pintype "passive"))
      (node (ref "R27") (pin "2") (pinfunction "2_2") (pintype "passive"))
    )
    (net (code "17") (name "Net-(C20-Pad+)") (class "Default")
      (node (ref "C20") (pin "+") (pinfunction "+_+") (pintype "passive"))
      (node (ref "R12") (pin "2") (pinfunction "2_2") (pintype "passive"))
      (node (ref "R13") (pin "1") (pinfunction "1_1") (pintype "passive"))
      (node (ref "R14") (pin "2") (pinfunction "2_2") (pintype "passive"))
    )
    (net (code "18") (name "Net-(C20-Pad-)") (class "Default")
      (node (ref "C20") (pin "-") (pinfunction "-_-") (pintype "passive"))
      (node (ref "C21") (pin "-") (pinfunction "-_-") (pintype "passive"))
      (node (ref "Q5") (pin "E") (pinfunction "E_E") (pintype "passive"))
      (node (ref "R10") (pin "2") (pinfunction "2_2") (pintype "passive"))
      (node (ref "R11") (pin "2") (pinfunction "2_2") (pintype "passive"))
    )
    (net (code "19") (name "Net-(C23-Pad1)") (class "Default")
      (node (ref "C23") (pin "1") (pinfunction "1_1") (pintype "passive"))
      (node (ref "D3") (pin "A") (pinfunction "A_A") (pintype "passive"))
      (node (ref "R18") (pin "2") (pinfunction "2_2") (pintype "passive"))
    )
    (net (code "20") (name "Net-(C28-Pad+)") (class "Default")
      (node (ref "C28") (pin "+") (pinfunction "+_+") (pintype "passive"))
      (node (ref "R39") (pin "1") (pinfunction "1_1") (pintype "passive"))
    )
    (net (code "21") (name "Net-(D1-PadA)") (class "Default")
      (node (ref "D1") (pin "A") (pinfunction "A_A") (pintype "passive"))
      (node (ref "D2") (pin "C") (pinfunction "C_C") (pintype "passive"))
      (node (ref "JP4") (pin "1") (pinfunction "1_1") (pintype "passive"))
    )
    (net (code "22") (name "Net-(D3-PadC)") (class "Default")
      (node (ref "D3") (pin "C") (pinfunction "C_C") (pintype "passive"))
      (node (ref "VOL_L1") (pin "P$2") (pinfunction "P$2_P$2") (pintype "bidirectional"))
      (node (ref "VOL_L2") (pin "P$1") (pinfunction "P$1_P$1") (pintype "bidirectional"))
    )
    (net (code "23") (name "Net-(D5-PadA)") (class "Default")
      (node (ref "D5") (pin "A") (pinfunction "A_A") (pintype "passive"))
      (node (ref "R30") (pin "1") (pinfunction "1_1") (pintype "passive"))
    )
    (net (code "24") (name "Net-(FPO(-0.6V)-PadP$1)") (class "Default")
      (node (ref "FPO(-0.6V)") (pin "P$1") (pinfunction "P$1_P$1") (pintype "bidirectional"))
      (node (ref "Q1") (pin "E") (pinfunction "E_E") (pintype "passive"))
      (node (ref "Q2") (pin "E") (pinfunction "E_E") (pintype "passive"))
      (node (ref "R2") (pin "2") (pinfunction "2_2") (pintype "passive"))
    )
    (net (code "25") (name "Net-(IC3A--IN)") (class "Default")
      (node (ref "IC3") (pin "4") (pinfunction "-IN_4") (pintype "input"))
      (node (ref "R31") (pin "1") (pinfunction "1_1") (pintype "passive"))
      (node (ref "R32") (pin "2") (pinfunction "2_2") (pintype "passive"))
      (node (ref "R34") (pin "2") (pinfunction "2_2") (pintype "passive"))
    )
    (net (code "26") (name "Net-(IC3A-AMP{slash}BIAS)") (class "Default")
      (node (ref "IC3") (pin "1") (pinfunction "AMP/BIAS_1") (pintype "passive"))
      (node (ref "R35") (pin "2") (pinfunction "2_2") (pintype "passive"))
      (node (ref "R36") (pin "2") (pinfunction "2_2") (pintype "passive"))
    )
    (net (code "27") (name "Net-(IC3A-BUFF{slash}IN)") (class "Default")
      (node (ref "C27") (pin "1") (pinfunction "1_1") (pintype "passive"))
      (node (ref "IC3") (pin "5") (pinfunction "OUT_5") (pintype "output"))
      (node (ref "IC3") (pin "7") (pinfunction "BUFF/IN_7") (pintype "input"))
      (node (ref "R37") (pin "2") (pinfunction "2_2") (pintype "passive"))
    )
    (net (code "28") (name "Net-(IC3A-BUFF{slash}OUT)") (class "Default")
      (node (ref "C28") (pin "-") (pinfunction "-_-") (pintype "passive"))
      (node (ref "IC3") (pin "8") (pinfunction "BUFF/OUT_8") (pintype "output"))
      (node (ref "R38") (pin "1") (pinfunction "1_1") (pintype "passive"))
    )
    (net (code "29") (name "Net-(IC3A-DIODE{slash}BIAS)") (class "Default")
      (node (ref "IC3") (pin "2") (pinfunction "DIODE/BIAS_2") (pintype "passive"))
      (node (ref "R33") (pin "2") (pinfunction "2_2") (pintype "passive"))
    )
    (net (code "30") (name "Net-(IC3B-AMP{slash}BIAS)") (class "Default")
      (node (ref "IC3") (pin "16") (pinfunction "AMP/BIAS_16") (pintype "passive"))
      (node (ref "R21") (pin "1") (pinfunction "1_1") (pintype "passive"))
    )
    (net (code "31") (name "Net-(IC3B-DIODE{slash}BIAS)") (class "Default")
      (node (ref "IC3") (pin "15") (pinfunction "DIODE/BIAS_15") (pintype "passive"))
      (node (ref "R23") (pin "1") (pinfunction "1_1") (pintype "passive"))
    )
    (net (code "32") (name "Net-(IC3B-OUT)") (class "Default")
      (node (ref "D5") (pin "C") (pinfunction "C_C") (pintype "passive"))
      (node (ref "IC3") (pin "12") (pinfunction "OUT_12") (pintype "output"))
      (node (ref "JP13") (pin "1") (pinfunction "1_1") (pintype "passive"))
    )
    (net (code "33") (name "Net-(J1-Pad1)") (class "Default")
      (node (ref "J1") (pin "1") (pinfunction "1_1") (pintype "bidirectional"))
      (node (ref "JP3") (pin "1") (pinfunction "1_1") (pintype "passive"))
    )
    (net (code "34") (name "Net-(JP14-Pad1)") (class "Default")
      (node (ref "JP14") (pin "1") (pinfunction "1_1") (pintype "passive"))
      (node (ref "R36") (pin "1") (pinfunction "1_1") (pintype "passive"))
    )
    (net (code "35") (name "Net-(LED1-PadA)") (class "Default")
      (node (ref "LED1") (pin "A") (pinfunction "A_A") (pintype "passive"))
      (node (ref "R41") (pin "1") (pinfunction "1_1") (pintype "passive"))
    )
    (net (code "36") (name "Net-(PITCH_L1-PadP$2)") (class "Default")
      (node (ref "PITCH_L1") (pin "P$2") (pinfunction "P$2_P$2") (pintype "bidirectional"))
      (node (ref "PITCH_L2") (pin "P$1") (pinfunction "P$1_P$1") (pintype "bidirectional"))
    )
    (net (code "37") (name "Net-(PITCH_L2-PadP$2)") (class "Default")
      (node (ref "PITCH_L2") (pin "P$2") (pinfunction "P$2_P$2") (pintype "bidirectional"))
      (node (ref "PITCH_L3") (pin "P$1") (pinfunction "P$1_P$1") (pintype "bidirectional"))
    )
    (net (code "38") (name "Net-(PITCH_L3-PadP$2)") (class "Default")
      (node (ref "PITCH_L3") (pin "P$2") (pinfunction "P$2_P$2") (pintype "bidirectional"))
      (node (ref "PITCH_L4") (pin "P$1") (pinfunction "P$1_P$1") (pintype "bidirectional"))
    )
    (net (code "39") (name "Net-(Q1-PadB)") (class "Default")
      (node (ref "Q1") (pin "B") (pinfunction "B_B") (pintype "passive"))
      (node (ref "R1") (pin "2") (pinfunction "2_2") (pintype "passive"))
    )
    (net (code "40") (name "Net-(Q2-PadB)") (class "Default")
      (node (ref "Q2") (pin "B") (pinfunction "B_B") (pintype "passive"))
      (node (ref "R3") (pin "1") (pinfunction "1_1") (pintype "passive"))
      (node (ref "R4") (pin "2") (pinfunction "2_2") (pintype "passive"))
    )
    (net (code "41") (name "Net-(Q3-PadB)") (class "Default")
      (node (ref "Q3") (pin "B") (pinfunction "B_B") (pintype "passive"))
      (node (ref "R5") (pin "2") (pinfunction "2_2") (pintype "passive"))
    )
    (net (code "42") (name "Net-(Q3-PadE)") (class "Default")
      (node (ref "Q3") (pin "E") (pinfunction "E_E") (pintype "passive"))
      (node (ref "Q4") (pin "E") (pinfunction "E_E") (pintype "passive"))
      (node (ref "R6") (pin "2") (pinfunction "2_2") (pintype "passive"))
      (node (ref "VPO(-0.6)") (pin "P$1") (pinfunction "P$1_P$1") (pintype "bidirectional"))
    )
    (net (code "43") (name "Net-(Q4-PadB)") (class "Default")
      (node (ref "Q4") (pin "B") (pinfunction "B_B") (pintype "passive"))
      (node (ref "R7") (pin "1") (pinfunction "1_1") (pintype "passive"))
      (node (ref "R8") (pin "2") (pinfunction "2_2") (pintype "passive"))
    )
    (net (code "44") (name "Net-(Q5-PadB)") (class "Default")
      (node (ref "Q5") (pin "B") (pinfunction "B_B") (pintype "passive"))
      (node (ref "R9") (pin "1") (pinfunction "1_1") (pintype "passive"))
    )
    (net (code "45") (name "Net-(Q6-PadB)") (class "Default")
      (node (ref "Q6") (pin "B") (pinfunction "B_B") (pintype "passive"))
      (node (ref "R16") (pin "2") (pinfunction "2_2") (pintype "passive"))
    )
    (net (code "46") (name "Net-(Q6-PadE)") (class "Default")
      (node (ref "Q6") (pin "E") (pinfunction "E_E") (pintype "passive"))
      (node (ref "Q7") (pin "E") (pinfunction "E_E") (pintype "passive"))
      (node (ref "R15") (pin "2") (pinfunction "2_2") (pintype "passive"))
      (node (ref "VOL_OSC(-0.6)") (pin "P$1") (pinfunction "P$1_P$1") (pintype "bidirectional"))
    )
    (net (code "47") (name "Net-(Q8-PadB)") (class "Default")
      (node (ref "Q8") (pin "B") (pinfunction "B_B") (pintype "passive"))
      (node (ref "R25") (pin "1") (pinfunction "1_1") (pintype "passive"))
    )
    (net (code "48") (name "Net-(U$2-2)") (class "Default")
      (node (ref "R7") (pin "2") (pinfunction "2_2") (pintype "passive"))
      (node (ref "U$2") (pin "P$2") (pinfunction "2_P$2") (pintype "passive"))
    )
    (net (code "49") (name "Net-(U$3-2)") (class "Default")
      (node (ref "R3") (pin "2") (pinfunction "2_2") (pintype "passive"))
      (node (ref "U$3") (pin "P$2") (pinfunction "2_P$2") (pintype "passive"))
    )
    (net (code "50") (name "Net-(VOL_L2-PadP$2)") (class "Default")
      (node (ref "VOL_L2") (pin "P$2") (pinfunction "P$2_P$2") (pintype "bidirectional"))
      (node (ref "VOL_L3") (pin "P$1") (pinfunction "P$1_P$1") (pintype "bidirectional"))
    )
    (net (code "51") (name "Net-(VOL_L3-PadP$2)") (class "Default")
      (node (ref "VOL_L3") (pin "P$2") (pinfunction "P$2_P$2") (pintype "bidirectional"))
      (node (ref "VOL_L4") (pin "P$1") (pinfunction "P$1_P$1") (pintype "bidirectional"))
    )
    (net (code "52") (name "PITCH_ANTENNA") (class "Default")
      (node (ref "C11") (pin "2") (pinfunction "2_2") (pintype "passive"))
      (node (ref "C14") (pin "1") (pinfunction "1_1") (pintype "passive"))
      (node (ref "L1") (pin "3") (pinfunction "3_3") (pintype "bidirectional"))
      (node (ref "PITCH_L4") (pin "P$2") (pinfunction "P$2_P$2") (pintype "bidirectional"))
      (node (ref "Q3") (pin "C") (pinfunction "C_C") (pintype "passive"))
      (node (ref "U$2") (pin "P$1") (pinfunction "1_P$1") (pintype "passive"))
    )
    (net (code "53") (name "PITCH_PREVIEW") (class "Default")
      (node (ref "C25") (pin "1") (pinfunction "1_1") (pintype "passive"))
      (node (ref "IC3") (pin "3") (pinfunction "+IN_3") (pintype "input"))
      (node (ref "JP8") (pin "1") (pinfunction "1_1") (pintype "passive"))
      (node (ref "PP") (pin "P$1") (pinfunction "P$1_P$1") (pintype "bidirectional"))
      (node (ref "R19") (pin "1") (pinfunction "1_1") (pintype "passive"))
      (node (ref "R20") (pin "2") (pinfunction "2_2") (pintype "passive"))
    )
    (net (code "54") (name "PITCH_TUNE") (class "Default")
      (node (ref "PITCH_TUNE") (pin "2") (pinfunction "P$2_2") (pintype "bidirectional"))
      (node (ref "R10") (pin "1") (pinfunction "1_1") (pintype "passive"))
    )
    (net (code "55") (name "PITCH_TUNING") (class "Default")
      (node (ref "C10") (pin "1") (pinfunction "1_1") (pintype "passive"))
      (node (ref "C15") (pin "1") (pinfunction "1_1") (pintype "passive"))
      (node (ref "C7") (pin "2") (pinfunction "2_2") (pintype "passive"))
      (node (ref "L2") (pin "3") (pinfunction "3_3") (pintype "bidirectional"))
      (node (ref "Q1") (pin "C") (pinfunction "C_C") (pintype "passive"))
      (node (ref "Q5") (pin "C") (pinfunction "C_C") (pintype "passive"))
      (node (ref "U$3") (pin "P$1") (pinfunction "1_P$1") (pintype "passive"))
    )
    (net (code "56") (name "VCA_PROC") (class "Default")
      (node (ref "C8") (pin "1") (pinfunction "1_1") (pintype "passive"))
      (node (ref "IC3") (pin "13") (pinfunction "-IN_13") (pintype "input"))
      (node (ref "R18") (pin "1") (pinfunction "1_1") (pintype "passive"))
      (node (ref "R22") (pin "1") (pinfunction "1_1") (pintype "passive"))
      (node (ref "R30") (pin "2") (pinfunction "2_2") (pintype "passive"))
    )
    (net (code "57") (name "VOLUME_ANTENNA") (class "Default")
      (node (ref "JP2") (pin "1") (pinfunction "1_1") (pintype "passive"))
      (node (ref "VOL_L4") (pin "P$2") (pinfunction "P$2_P$2") (pintype "bidirectional"))
    )
    (net (code "58") (name "VOLUME_TUNE") (class "Default")
      (node (ref "R26") (pin "1") (pinfunction "1_1") (pintype "passive"))
      (node (ref "VOL_TUNE") (pin "2") (pinfunction "P$2_2") (pintype "bidirectional"))
    )
    (net (code "59") (name "VOLUME_TUNING") (class "Default")
      (node (ref "C12") (pin "1") (pinfunction "1_1") (pintype "passive"))
      (node (ref "C17") (pin "1") (pinfunction "1_1") (pintype "passive"))
      (node (ref "L3") (pin "1") (pinfunction "1_1") (pintype "bidirectional"))
      (node (ref "Q6") (pin "C") (pinfunction "C_C") (pintype "passive"))
      (node (ref "Q8") (pin "C") (pinfunction "C_C") (pintype "passive"))
    )
    (net (code "60") (name "VOL_ANT") (class "Default")
      (node (ref "C12") (pin "2") (pinfunction "2_2") (pintype "passive"))
      (node (ref "C23") (pin "2") (pinfunction "2_2") (pintype "passive"))
      (node (ref "Q7") (pin "B") (pinfunction "B_B") (pintype "passive"))
      (node (ref "R17") (pin "2") (pinfunction "2_2") (pintype "passive"))
      (node (ref "U$1") (pin "P$1") (pinfunction "1_P$1") (pintype "passive"))
      (node (ref "VOL_L1") (pin "P$1") (pinfunction "P$1_P$1") (pintype "bidirectional"))
    )
    (net (code "61") (name "VPO_OUT") (class "Default")
      (node (ref "C14") (pin "2") (pinfunction "2_2") (pintype "passive"))
      (node (ref "JP11") (pin "1") (pinfunction "1_1") (pintype "passive"))
    )
    (net (code "62") (name "WAVEFORM") (class "Default")
      (node (ref "R31") (pin "2") (pinfunction "2_2") (pintype "passive"))
      (node (ref "WAVEFORM") (pin "2") (pinfunction "P$2_2") (pintype "bidirectional"))
    )
  )
)
